# untitled.net
KiCad netlist of a schematic drawn in EAGLE
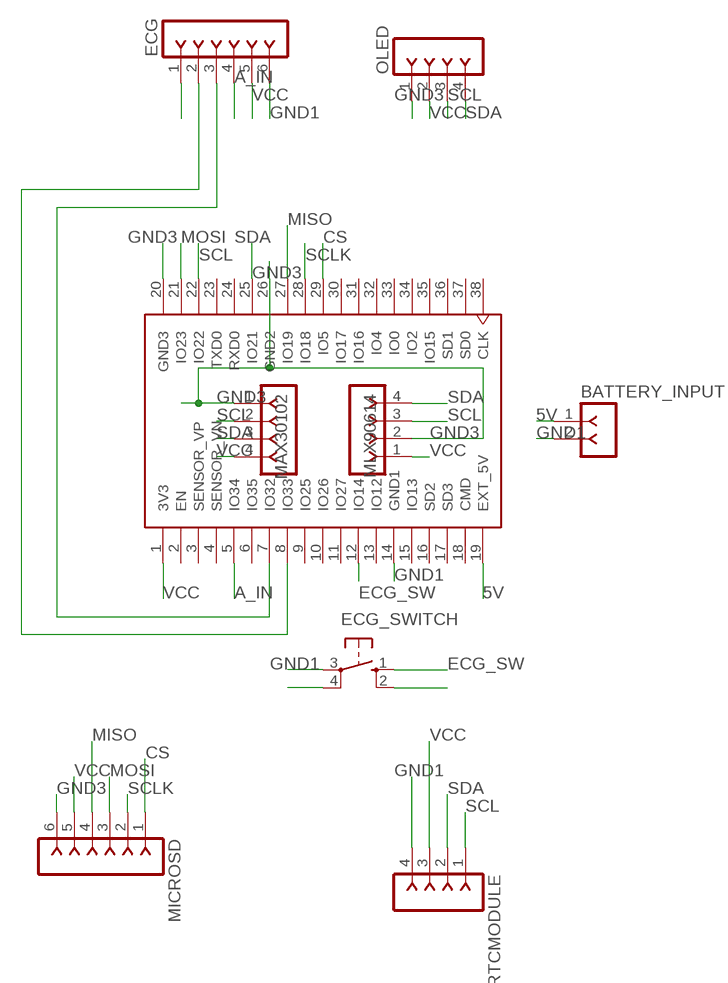
[diagram p0: schematic, sheet 1]

(export (version "E")
  (design (tool "Eeschema 10.0.6"))
  (components
    (comp (ref "BATTERY_INPUT")
      (value "F-1X02-SIP-100-40")
      (footprint "eagle-import:SIP-100-02-40")
      (libsource (lib "eagle-import") (part "F-1X02-SIP-100-40"))
    )
    (comp (ref "ECG")
      (value "F-1X06-SIP-100-40")
      (footprint "eagle-import:SIP-100-06-40")
      (libsource (lib "eagle-import") (part "F-1X06-SIP-100-40"))
    )
    (comp (ref "ECG_SWITCH")
      (value "10-XX")
      (footprint "eagle-import:B3F-10XX")
      (fields (field (name "MPN") "B3F-1000"))
      (libsource (lib "eagle-import") (part "10-XX"))
    )
    (comp (ref "MAX30102")
      (value "F-1X04-SIP-100-40")
      (footprint "eagle-import:SIP-100-04-40")
      (libsource (lib "eagle-import") (part "F-1X04-SIP-100-40"))
    )
    (comp (ref "MICROSD")
      (value "F-1X06-SIP-100-40")
      (footprint "eagle-import:SIP-100-06-40")
      (libsource (lib "eagle-import") (part "F-1X06-SIP-100-40"))
    )
    (comp (ref "MLX90614")
      (value "F-1X04-SIP-100-40")
      (footprint "eagle-import:SIP-100-04-40")
      (libsource (lib "eagle-import") (part "F-1X04-SIP-100-40"))
    )
    (comp (ref "OLED")
      (value "F-1X04-SIP-100-40")
      (footprint "eagle-import:SIP-100-04-40")
      (libsource (lib "eagle-import") (part "F-1X04-SIP-100-40"))
    )
    (comp (ref "RTCMODULE")
      (value "F-1X04-SIP-100-40")
      (footprint "eagle-import:SIP-100-04-40")
      (libsource (lib "eagle-import") (part "F-1X04-SIP-100-40"))
    )
    (comp (ref "U1")
      (value "ESP32-DEVKITC-32D")
      (footprint "eagle-import:MODULE_ESP32-DEVKITC-32D")
      (fields (field (name "MF") "Espressif Systems"))
      (libsource (lib "eagle-import") (part "ESP32-DEVKITC-32D"))
    )
  )
  (nets
    (net (code "1") (name "/5V") (class "Default")
      (node (ref "BATTERY_INPUT") (pin "1") (pinfunction "1_1") (pintype "passive"))
      (node (ref "U1") (pin "19") (pinfunction "EXT_5V_19") (pintype "power_in"))
    )
    (net (code "2") (name "/A_IN") (class "Default")
      (node (ref "ECG") (pin "4") (pinfunction "4_4") (pintype "passive"))
      (node (ref "U1") (pin "5") (pinfunction "IO34_5") (pintype "bidirectional"))
    )
    (net (code "3") (name "/CS") (class "Default")
      (node (ref "MICROSD") (pin "1") (pinfunction "1_1") (pintype "passive"))
      (node (ref "U1") (pin "29") (pinfunction "IO5_29") (pintype "bidirectional"))
    )
    (net (code "4") (name "/ECG_SW") (class "Default")
      (node (ref "ECG_SWITCH") (pin "1") (pinfunction "S_1") (pintype "passive"))
      (node (ref "U1") (pin "12") (pinfunction "IO14_12") (pintype "bidirectional"))
    )
    (net (code "5") (name "/GND1") (class "Default")
      (node (ref "BATTERY_INPUT") (pin "2") (pinfunction "2_2") (pintype "passive"))
      (node (ref "ECG") (pin "6") (pinfunction "6_6") (pintype "passive"))
      (node (ref "ECG_SWITCH") (pin "3") (pinfunction "P_3") (pintype "passive"))
      (node (ref "RTCMODULE") (pin "4") (pinfunction "4_4") (pintype "passive"))
      (node (ref "U1") (pin "14") (pinfunction "GND1_14") (pintype "power_in"))
    )
    (net (code "6") (name "/GND3") (class "Default")
      (node (ref "MAX30102") (pin "1") (pinfunction "1_1") (pintype "passive"))
      (node (ref "MICROSD") (pin "6") (pinfunction "6_6") (pintype "passive"))
      (node (ref "MLX90614") (pin "2") (pinfunction "2_2") (pintype "passive"))
      (node (ref "OLED") (pin "1") (pinfunction "1_1") (pintype "passive"))
      (node (ref "U1") (pin "20") (pinfunction "GND3_20") (pintype "power_in"))
      (node (ref "U1") (pin "26") (pinfunction "GND2_26") (pintype "power_in"))
    )
    (net (code "7") (name "/MISO") (class "Default")
      (node (ref "MICROSD") (pin "4") (pinfunction "4_4") (pintype "passive"))
      (node (ref "U1") (pin "27") (pinfunction "IO19_27") (pintype "bidirectional"))
    )
    (net (code "8") (name "/MOSI") (class "Default")
      (node (ref "MICROSD") (pin "3") (pinfunction "3_3") (pintype "passive"))
      (node (ref "U1") (pin "21") (pinfunction "IO23_21") (pintype "bidirectional"))
    )
    (net (code "9") (name "/SCL") (class "Default")
      (node (ref "MAX30102") (pin "2") (pinfunction "2_2") (pintype "passive"))
      (node (ref "MLX90614") (pin "3") (pinfunction "3_3") (pintype "passive"))
      (node (ref "OLED") (pin "3") (pinfunction "3_3") (pintype "passive"))
      (node (ref "RTCMODULE") (pin "1") (pinfunction "1_1") (pintype "passive"))
      (node (ref "U1") (pin "22") (pinfunction "IO22_22") (pintype "bidirectional"))
    )
    (net (code "10") (name "/SCLK") (class "Default")
      (node (ref "MICROSD") (pin "2") (pinfunction "2_2") (pintype "passive"))
      (node (ref "U1") (pin "28") (pinfunction "IO18_28") (pintype "bidirectional"))
    )
    (net (code "11") (name "/SDA") (class "Default")
      (node (ref "MAX30102") (pin "3") (pinfunction "3_3") (pintype "passive"))
      (node (ref "MLX90614") (pin "4") (pinfunction "4_4") (pintype "passive"))
      (node (ref "OLED") (pin "4") (pinfunction "4_4") (pintype "passive"))
      (node (ref "RTCMODULE") (pin "2") (pinfunction "2_2") (pintype "passive"))
      (node (ref "U1") (pin "25") (pinfunction "IO21_25") (pintype "bidirectional"))
    )
    (net (code "12") (name "/VCC") (class "Default")
      (node (ref "ECG") (pin "5") (pinfunction "5_5") (pintype "passive"))
      (node (ref "MAX30102") (pin "4") (pinfunction "4_4") (pintype "passive"))
      (node (ref "MICROSD") (pin "5") (pinfunction "5_5") (pintype "passive"))
      (node (ref "MLX90614") (pin "1") (pinfunction "1_1") (pintype "passive"))
      (node (ref "OLED") (pin "2") (pinfunction "2_2") (pintype "passive"))
      (node (ref "RTCMODULE") (pin "3") (pinfunction "3_3") (pintype "passive"))
      (node (ref "U1") (pin "1") (pinfunction "3V3_1") (pintype "power_in"))
    )
    (net (code "13") (name "Net-(U1-IO32)") (class "Default")
      (node (ref "ECG") (pin "3") (pinfunction "3_3") (pintype "passive"))
      (node (ref "U1") (pin "7") (pinfunction "IO32_7") (pintype "bidirectional"))
    )
    (net (code "14") (name "Net-(U1-IO33)") (class "Default")
      (node (ref "ECG") (pin "2") (pinfunction "2_2") (pintype "passive"))
      (node (ref "U1") (pin "8") (pinfunction "IO33_8") (pintype "bidirectional"))
    )
    (net (code "15") (name "unconnected-(ECG-Pad1)") (class "Default")
      (node (ref "ECG") (pin "1") (pinfunction "1_1") (pintype "passive"))
    )
    (net (code "16") (name "unconnected-(ECG_SWITCH-P1-Pad4)") (class "Default")
      (node (ref "ECG_SWITCH") (pin "4") (pinfunction "P1_4") (pintype "passive"))
    )
    (net (code "17") (name "unconnected-(ECG_SWITCH-S1-Pad2)") (class "Default")
      (node (ref "ECG_SWITCH") (pin "2") (pinfunction "S1_2") (pintype "passive"))
    )
    (net (code "18") (name "unconnected-(U1-CLK-Pad38)") (class "Default")
      (node (ref "U1") (pin "38") (pinfunction "CLK_38") (pintype "input"))
    )
    (net (code "19") (name "unconnected-(U1-CMD-Pad18)") (class "Default")
      (node (ref "U1") (pin "18") (pinfunction "CMD_18") (pintype "bidirectional"))
    )
    (net (code "20") (name "unconnected-(U1-EN-Pad2)") (class "Default")
      (node (ref "U1") (pin "2") (pinfunction "EN_2") (pintype "input"))
    )
    (net (code "21") (name "unconnected-(U1-IO0-Pad33)") (class "Default")
      (node (ref "U1") (pin "33") (pinfunction "IO0_33") (pintype "bidirectional"))
    )
    (net (code "22") (name "unconnected-(U1-IO2-Pad34)") (class "Default")
      (node (ref "U1") (pin "34") (pinfunction "IO2_34") (pintype "bidirectional"))
    )
    (net (code "23") (name "unconnected-(U1-IO4-Pad32)") (class "Default")
      (node (ref "U1") (pin "32") (pinfunction "IO4_32") (pintype "bidirectional"))
    )
    (net (code "24") (name "unconnected-(U1-IO12-Pad13)") (class "Default")
      (node (ref "U1") (pin "13") (pinfunction "IO12_13") (pintype "bidirectional"))
    )
    (net (code "25") (name "unconnected-(U1-IO13-Pad15)") (class "Default")
      (node (ref "U1") (pin "15") (pinfunction "IO13_15") (pintype "bidirectional"))
    )
    (net (code "26") (name "unconnected-(U1-IO15-Pad35)") (class "Default")
      (node (ref "U1") (pin "35") (pinfunction "IO15_35") (pintype "bidirectional"))
    )
    (net (code "27") (name "unconnected-(U1-IO16-Pad31)") (class "Default")
      (node (ref "U1") (pin "31") (pinfunction "IO16_31") (pintype "bidirectional"))
    )
    (net (code "28") (name "unconnected-(U1-IO17-Pad30)") (class "Default")
      (node (ref "U1") (pin "30") (pinfunction "IO17_30") (pintype "bidirectional"))
    )
    (net (code "29") (name "unconnected-(U1-IO25-Pad9)") (class "Default")
      (node (ref "U1") (pin "9") (pinfunction "IO25_9") (pintype "bidirectional"))
    )
    (net (code "30") (name "unconnected-(U1-IO26-Pad10)") (class "Default")
      (node (ref "U1") (pin "10") (pinfunction "IO26_10") (pintype "bidirectional"))
    )
    (net (code "31") (name "unconnected-(U1-IO27-Pad11)") (class "Default")
      (node (ref "U1") (pin "11") (pinfunction "IO27_11") (pintype "bidirectional"))
    )
    (net (code "32") (name "unconnected-(U1-IO35-Pad6)") (class "Default")
      (node (ref "U1") (pin "6") (pinfunction "IO35_6") (pintype "bidirectional"))
    )
    (net (code "33") (name "unconnected-(U1-RXD0-Pad24)") (class "Default")
      (node (ref "U1") (pin "24") (pinfunction "RXD0_24") (pintype "input"))
    )
    (net (code "34") (name "unconnected-(U1-SD0-Pad37)") (class "Default")
      (node (ref "U1") (pin "37") (pinfunction "SD0_37") (pintype "bidirectional"))
    )
    (net (code "35") (name "unconnected-(U1-SD1-Pad36)") (class "Default")
      (node (ref "U1") (pin "36") (pinfunction "SD1_36") (pintype "bidirectional"))
    )
    (net (code "36") (name "unconnected-(U1-SD2-Pad16)") (class "Default")
      (node (ref "U1") (pin "16") (pinfunction "SD2_16") (pintype "bidirectional"))
    )
    (net (code "37") (name "unconnected-(U1-SD3-Pad17)") (class "Default")
      (node (ref "U1") (pin "17") (pinfunction "SD3_17") (pintype "bidirectional"))
    )
    (net (code "38") (name "unconnected-(U1-SENSOR_VN-Pad4)") (class "Default")
      (node (ref "U1") (pin "4") (pinfunction "SENSOR_VN_4") (pintype "input"))
    )
    (net (code "39") (name "unconnected-(U1-SENSOR_VP-Pad3)") (class "Default")
      (node (ref "U1") (pin "3") (pinfunction "SENSOR_VP_3") (pintype "input"))
    )
    (net (code "40") (name "unconnected-(U1-TXD0-Pad23)") (class "Default")
      (node (ref "U1") (pin "23") (pinfunction "TXD0_23") (pintype "output"))
    )
  )
)
